# heartbeat.net
KiCad netlist of a schematic drawn in EAGLE
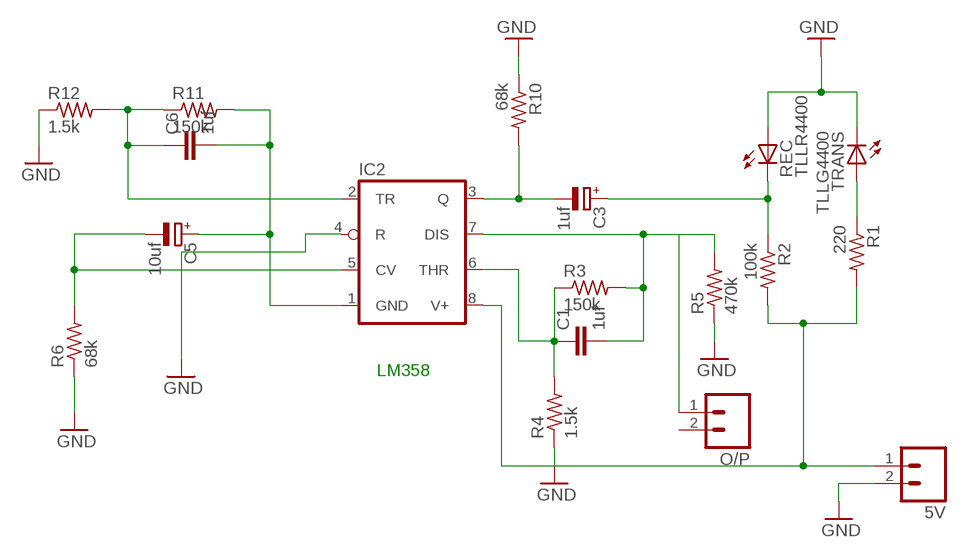
[diagram p0: schematic, sheet 1]

(export (version "E")
  (design (tool "Eeschema 10.0.6"))
  (components
    (comp (ref "5V")
      (value "M02")
      (footprint "eagle-import:02P")
      (libsource (lib "eagle-import") (part "M02"))
    )
    (comp (ref "C1")
      (value "1uf")
      (footprint "eagle-import:C025-030X050")
      (libsource (lib "eagle-import") (part "C-EU025-030X050"))
    )
    (comp (ref "C3")
      (value "1uf")
      (footprint "eagle-import:TT2D4")
      (libsource (lib "eagle-import") (part "CPOL-EUTT2D4"))
    )
    (comp (ref "C5")
      (value "10uf")
      (footprint "eagle-import:TT2D4")
      (libsource (lib "eagle-import") (part "CPOL-EUTT2D4"))
    )
    (comp (ref "C6")
      (value "1uf")
      (footprint "eagle-import:C025-030X050")
      (libsource (lib "eagle-import") (part "C-EU025-030X050"))
    )
    (comp (ref "IC2")
      (value "LM555N")
      (footprint "eagle-import:DIL08-ROUND")
      (libsource (lib "eagle-import") (part "555NLM"))
    )
    (comp (ref "O/P")
      (value "M02")
      (footprint "eagle-import:02P")
      (libsource (lib "eagle-import") (part "M02"))
    )
    (comp (ref "R1")
      (value "220")
      (footprint "eagle-import:0207_10")
      (libsource (lib "eagle-import") (part "R-US_0207/10"))
    )
    (comp (ref "R2")
      (value "100k")
      (footprint "eagle-import:0207_10")
      (libsource (lib "eagle-import") (part "R-US_0207/10"))
    )
    (comp (ref "R3")
      (value "150k")
      (footprint "eagle-import:0207_10")
      (libsource (lib "eagle-import") (part "R-US_0207/10"))
    )
    (comp (ref "R4")
      (value "1.5k")
      (footprint "eagle-import:0207_10")
      (libsource (lib "eagle-import") (part "R-US_0207/10"))
    )
    (comp (ref "R5")
      (value "470k")
      (footprint "eagle-import:0207_10")
      (libsource (lib "eagle-import") (part "R-US_0207/10"))
    )
    (comp (ref "R6")
      (value "68k")
      (footprint "eagle-import:0207_10")
      (libsource (lib "eagle-import") (part "R-US_0207/10"))
    )
    (comp (ref "R10")
      (value "68k")
      (footprint "eagle-import:0207_10")
      (libsource (lib "eagle-import") (part "R-US_0207/10"))
    )
    (comp (ref "R11")
      (value "150k")
      (footprint "eagle-import:0207_10")
      (libsource (lib "eagle-import") (part "R-US_0207/10"))
    )
    (comp (ref "R12")
      (value "1.5k")
      (footprint "eagle-import:0207_10")
      (libsource (lib "eagle-import") (part "R-US_0207/10"))
    )
    (comp (ref "REC")
      (value "TLLR4400")
      (footprint "eagle-import:LED3MM")
      (fields (field (name "MF") "VISHAY SEMICONDUCTOR"))
      (libsource (lib "eagle-import") (part "TLLR4400"))
    )
    (comp (ref "TRANS")
      (value "TLLG4400")
      (footprint "eagle-import:LED3MM")
      (fields (field (name "MF") "VISHAY SEMICONDUCTOR"))
      (libsource (lib "eagle-import") (part "TLLG4400"))
    )
  )
  (nets
    (net (code "1") (name "GND") (class "Default")
      (node (ref "5V") (pin "2") (pinfunction "2_2") (pintype "passive"))
      (node (ref "IC2") (pin "4") (pinfunction "R_4") (pintype "input"))
      (node (ref "R10") (pin "1") (pinfunction "1_1") (pintype "passive"))
      (node (ref "R12") (pin "1") (pinfunction "1_1") (pintype "passive"))
      (node (ref "R4") (pin "1") (pinfunction "1_1") (pintype "passive"))
      (node (ref "R5") (pin "1") (pinfunction "1_1") (pintype "passive"))
      (node (ref "R6") (pin "1") (pinfunction "1_1") (pintype "passive"))
      (node (ref "REC") (pin "A") (pinfunction "A_A") (pintype "passive"))
      (node (ref "TRANS") (pin "K") (pinfunction "C_K") (pintype "passive"))
    )
    (net (code "2") (name "Net-(IC2-CV)") (class "Default")
      (node (ref "C5") (pin "-") (pinfunction "-_-") (pintype "passive"))
      (node (ref "IC2") (pin "5") (pinfunction "CV_5") (pintype "input"))
      (node (ref "R6") (pin "2") (pinfunction "2_2") (pintype "passive"))
    )
    (net (code "3") (name "Net-(IC2-DIS)") (class "Default")
      (node (ref "C1") (pin "2") (pinfunction "2_2") (pintype "passive"))
      (node (ref "IC2") (pin "7") (pinfunction "DIS_7") (pintype "input"))
      (node (ref "O/P") (pin "1") (pinfunction "1_1") (pintype "passive"))
      (node (ref "R3") (pin "2") (pinfunction "2_2") (pintype "passive"))
      (node (ref "R5") (pin "2") (pinfunction "2_2") (pintype "passive"))
    )
    (net (code "4") (name "Net-(IC2-GND)") (class "Default")
      (node (ref "C5") (pin "+") (pinfunction "+_+") (pintype "passive"))
      (node (ref "C6") (pin "2") (pinfunction "2_2") (pintype "passive"))
      (node (ref "IC2") (pin "1") (pinfunction "GND_1") (pintype "power_in"))
      (node (ref "R11") (pin "2") (pinfunction "2_2") (pintype "passive"))
    )
    (net (code "5") (name "Net-(IC2-Q)") (class "Default")
      (node (ref "C3") (pin "-") (pinfunction "-_-") (pintype "passive"))
      (node (ref "IC2") (pin "3") (pinfunction "Q_3") (pintype "output"))
      (node (ref "R10") (pin "2") (pinfunction "2_2") (pintype "passive"))
    )
    (net (code "6") (name "Net-(IC2-THR)") (class "Default")
      (node (ref "C1") (pin "1") (pinfunction "1_1") (pintype "passive"))
      (node (ref "IC2") (pin "6") (pinfunction "THR_6") (pintype "input"))
      (node (ref "R3") (pin "1") (pinfunction "1_1") (pintype "passive"))
      (node (ref "R4") (pin "2") (pinfunction "2_2") (pintype "passive"))
    )
    (net (code "7") (name "Net-(IC2-TR)") (class "Default")
      (node (ref "C6") (pin "1") (pinfunction "1_1") (pintype "passive"))
      (node (ref "IC2") (pin "2") (pinfunction "TR_2") (pintype "input"))
      (node (ref "R11") (pin "1") (pinfunction "1_1") (pintype "passive"))
      (node (ref "R12") (pin "2") (pinfunction "2_2") (pintype "passive"))
    )
    (net (code "8") (name "Net-(IC2-V+)") (class "Default")
      (node (ref "5V") (pin "1") (pinfunction "1_1") (pintype "passive"))
      (node (ref "IC2") (pin "8") (pinfunction "V+_8") (pintype "power_in"))
      (node (ref "R1") (pin "2") (pinfunction "2_2") (pintype "passive"))
      (node (ref "R2") (pin "2") (pinfunction "2_2") (pintype "passive"))
    )
    (net (code "9") (name "Net-(R1-Pad1)") (class "Default")
      (node (ref "R1") (pin "1") (pinfunction "1_1") (pintype "passive"))
      (node (ref "TRANS") (pin "A") (pinfunction "A_A") (pintype "passive"))
    )
    (net (code "10") (name "Net-(REC-C)") (class "Default")
      (node (ref "C3") (pin "+") (pinfunction "+_+") (pintype "passive"))
      (node (ref "R2") (pin "1") (pinfunction "1_1") (pintype "passive"))
      (node (ref "REC") (pin "K") (pinfunction "C_K") (pintype "passive"))
    )
    (net (code "11") (name "unconnected-(O/P-Pad2)") (class "Default")
      (node (ref "O/P") (pin "2") (pinfunction "2_2") (pintype "passive"))
    )
  )
)
